# pmm.net
KiCad netlist of a schematic drawn in EAGLE
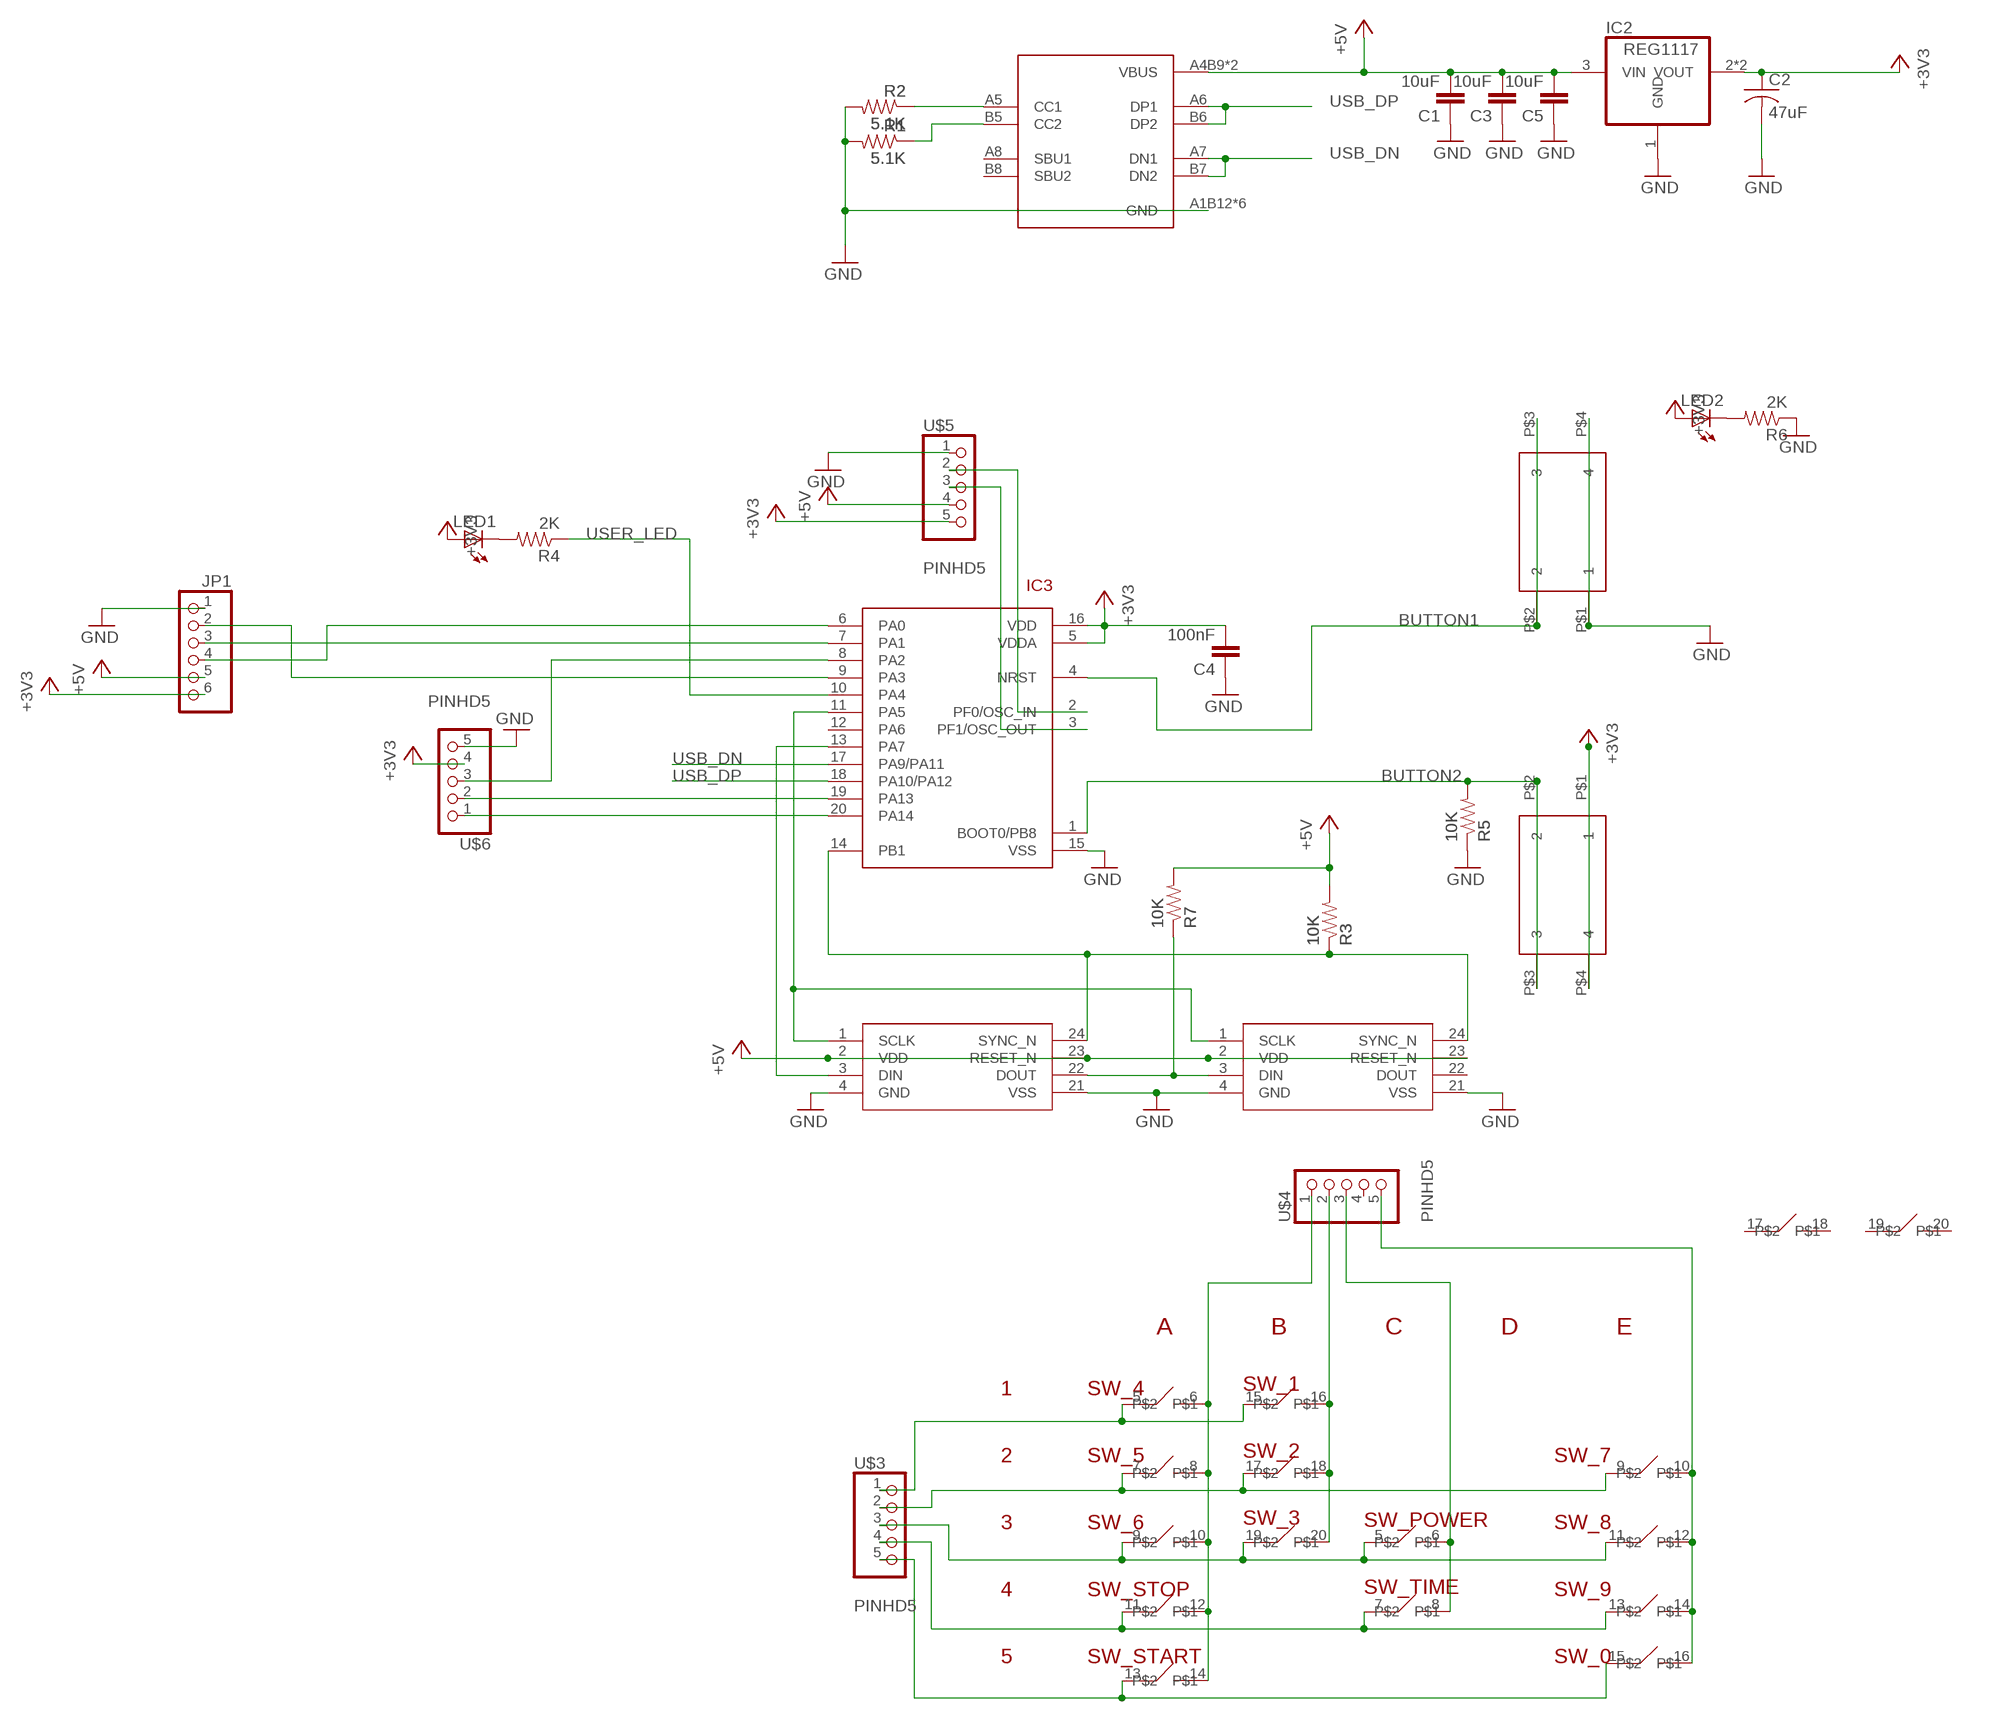
[diagram p0: schematic, sheet 1]

(export (version "E")
  (design (tool "Eeschema 10.0.6"))
  (components
    (comp (ref "C1")
      (value "10uF")
      (footprint "eagle-import:0805@1")
      (libsource (lib "eagle-import") (part "CAP0805"))
    )
    (comp (ref "C2")
      (value "47uF")
      (footprint "eagle-import:C1210")
      (libsource (lib "eagle-import") (part "C-USC1210"))
    )
    (comp (ref "C3")
      (value "10uF")
      (footprint "eagle-import:0805@1")
      (libsource (lib "eagle-import") (part "CAP0805"))
    )
    (comp (ref "C4")
      (value "100nF")
      (footprint "eagle-import:0805@1")
      (libsource (lib "eagle-import") (part "CAP0805"))
    )
    (comp (ref "C5")
      (value "10uF")
      (footprint "eagle-import:0805@1")
      (libsource (lib "eagle-import") (part "CAP0805"))
    )
    (comp (ref "IC2")
      (value "REG1117")
      (footprint "eagle-import:SOT223")
      (libsource (lib "eagle-import") (part "REG1117"))
    )
    (comp (ref "IC3")
      (value "STM32F042F4")
      (footprint "eagle-import:TSSOP20")
      (libsource (lib "eagle-import") (part "STM32F042F4"))
    )
    (comp (ref "JP1")
      (value "PINHD-1X6CB")
      (footprint "eagle-import:1X06-CLEANBIG")
      (libsource (lib "eagle-import") (part "PINHD-1X6CB"))
    )
    (comp (ref "LED1")
      (value "LEDCHIP-LED0805")
      (footprint "eagle-import:CHIP-LED0805")
      (libsource (lib "eagle-import") (part "LEDCHIP-LED0805"))
    )
    (comp (ref "LED2")
      (value "LEDCHIP-LED0805")
      (footprint "eagle-import:CHIP-LED0805")
      (libsource (lib "eagle-import") (part "LEDCHIP-LED0805"))
    )
    (comp (ref "R1")
      (value "5.1K")
      (footprint "eagle-import:0805")
      (libsource (lib "eagle-import") (part "joyAnalog_RESISTOR0805-RES"))
    )
    (comp (ref "R2")
      (value "5.1K")
      (footprint "eagle-import:0805")
      (libsource (lib "eagle-import") (part "joyAnalog_RESISTOR0805-RES"))
    )
    (comp (ref "R3")
      (value "10K")
      (footprint "eagle-import:0805")
      (libsource (lib "eagle-import") (part "joyAnalog_RESISTOR0805-RES"))
    )
    (comp (ref "R4")
      (value "2K")
      (footprint "eagle-import:0805")
      (libsource (lib "eagle-import") (part "RESISTOR0805-RES"))
    )
    (comp (ref "R5")
      (value "10K")
      (footprint "eagle-import:0805")
      (libsource (lib "eagle-import") (part "joyAnalog_RESISTOR0805-RES"))
    )
    (comp (ref "R6")
      (value "2K")
      (footprint "eagle-import:0805")
      (libsource (lib "eagle-import") (part "RESISTOR0805-RES"))
    )
    (comp (ref "R7")
      (value "10K")
      (footprint "eagle-import:0805")
      (libsource (lib "eagle-import") (part "joyAnalog_RESISTOR0805-RES"))
    )
    (comp (ref "SW3")
      (value "324_SW")
      (footprint "eagle-import:342_SWICH_FOOT")
      (libsource (lib "eagle-import") (part "324_SW"))
    )
    (comp (ref "SW4")
      (value "324_SW")
      (footprint "eagle-import:342_SWICH_FOOT")
      (libsource (lib "eagle-import") (part "324_SW"))
    )
    (comp (ref "U$1")
      (value "ADG714_SEPERATE")
      (footprint "eagle-import:TSSOP-24")
      (libsource (lib "eagle-import") (part "ADG714_SEPERATE"))
    )
    (comp (ref "U$2")
      (value "ADG714_SEPERATE")
      (footprint "eagle-import:TSSOP-24")
      (libsource (lib "eagle-import") (part "ADG714_SEPERATE"))
    )
    (comp (ref "U$3")
      (value "PINHD5")
      (footprint "eagle-import:1X05")
      (libsource (lib "eagle-import") (part "PINHD5"))
    )
    (comp (ref "U$4")
      (value "PINHD5")
      (footprint "eagle-import:1X05")
      (libsource (lib "eagle-import") (part "PINHD5"))
    )
    (comp (ref "U$5")
      (value "PINHD5")
      (footprint "eagle-import:1X05")
      (libsource (lib "eagle-import") (part "PINHD5"))
    )
    (comp (ref "U$6")
      (value "PINHD5")
      (footprint "eagle-import:1X05")
      (libsource (lib "eagle-import") (part "PINHD5"))
    )
    (comp (ref "U2")
      (value "USBC_16P")
      (footprint "eagle-import:USBC_16P_FOOT")
      (libsource (lib "eagle-import") (part "USBC_16P"))
    )
  )
  (nets
    (net (code "1") (name "+3V3") (class "Default")
      (node (ref "C2") (pin "1") (pinfunction "1_1") (pintype "passive"))
      (node (ref "C4") (pin "2") (pinfunction "2_2") (pintype "passive"))
      (node (ref "IC2") (pin "2") (pinfunction "VOUT_2") (pintype "output"))
      (node (ref "IC2") (pin "4") (pinfunction "VOUT_4") (pintype "output"))
      (node (ref "IC3") (pin "16") (pinfunction "VDD_16") (pintype "bidirectional"))
      (node (ref "IC3") (pin "5") (pinfunction "VDDA_5") (pintype "bidirectional"))
      (node (ref "JP1") (pin "6") (pinfunction "6_6") (pintype "passive"))
      (node (ref "LED1") (pin "A") (pinfunction "A_A") (pintype "passive"))
      (node (ref "LED2") (pin "A") (pinfunction "A_A") (pintype "passive"))
      (node (ref "SW4") (pin "P$1") (pinfunction "1_P$1") (pintype "bidirectional"))
      (node (ref "SW4") (pin "P$4") (pinfunction "4_P$4") (pintype "bidirectional"))
      (node (ref "U$5") (pin "5") (pinfunction "5_5") (pintype "passive"))
      (node (ref "U$6") (pin "4") (pinfunction "4_4") (pintype "passive"))
    )
    (net (code "2") (name "+5V") (class "Default")
      (node (ref "C1") (pin "2") (pinfunction "2_2") (pintype "passive"))
      (node (ref "C3") (pin "2") (pinfunction "2_2") (pintype "passive"))
      (node (ref "C5") (pin "2") (pinfunction "2_2") (pintype "passive"))
      (node (ref "IC2") (pin "3") (pinfunction "VIN_3") (pintype "input"))
      (node (ref "JP1") (pin "5") (pinfunction "5_5") (pintype "passive"))
      (node (ref "R3") (pin "2") (pinfunction "2_2") (pintype "passive"))
      (node (ref "R7") (pin "2") (pinfunction "2_2") (pintype "passive"))
      (node (ref "U$1") (pin "2") (pinfunction "VDD_2") (pintype "bidirectional"))
      (node (ref "U$1") (pin "23") (pinfunction "RESET_N_23") (pintype "bidirectional"))
      (node (ref "U$2") (pin "2") (pinfunction "VDD_2") (pintype "bidirectional"))
      (node (ref "U$2") (pin "23") (pinfunction "RESET_N_23") (pintype "bidirectional"))
      (node (ref "U$5") (pin "4") (pinfunction "4_4") (pintype "passive"))
      (node (ref "U2") (pin "A4B9") (pinfunction "VBUS_A4B9") (pintype "bidirectional"))
      (node (ref "U2") (pin "B4A9") (pinfunction "VBUS_B4A9") (pintype "bidirectional"))
    )
    (net (code "3") (name "/BUTTON1") (class "Default")
      (node (ref "IC3") (pin "4") (pinfunction "NRST_4") (pintype "bidirectional"))
      (node (ref "SW3") (pin "P$2") (pinfunction "2_P$2") (pintype "bidirectional"))
      (node (ref "SW3") (pin "P$3") (pinfunction "3_P$3") (pintype "bidirectional"))
    )
    (net (code "4") (name "/BUTTON2") (class "Default")
      (node (ref "IC3") (pin "1") (pinfunction "BOOT0/PB8_1") (pintype "bidirectional"))
      (node (ref "R5") (pin "2") (pinfunction "2_2") (pintype "passive"))
      (node (ref "SW4") (pin "P$2") (pinfunction "2_P$2") (pintype "bidirectional"))
      (node (ref "SW4") (pin "P$3") (pinfunction "3_P$3") (pintype "bidirectional"))
    )
    (net (code "5") (name "/USB_DN") (class "Default")
      (node (ref "IC3") (pin "17") (pinfunction "PA9/PA11_17") (pintype "bidirectional"))
      (node (ref "U2") (pin "A7") (pinfunction "DN1_A7") (pintype "bidirectional"))
      (node (ref "U2") (pin "B7") (pinfunction "DN2_B7") (pintype "bidirectional"))
    )
    (net (code "6") (name "/USB_DP") (class "Default")
      (node (ref "IC3") (pin "18") (pinfunction "PA10/PA12_18") (pintype "bidirectional"))
      (node (ref "U2") (pin "A6") (pinfunction "DP1_A6") (pintype "bidirectional"))
      (node (ref "U2") (pin "B6") (pinfunction "DP2_B6") (pintype "bidirectional"))
    )
    (net (code "7") (name "/USER_LED") (class "Default")
      (node (ref "IC3") (pin "10") (pinfunction "PA4_10") (pintype "bidirectional"))
      (node (ref "R4") (pin "1") (pinfunction "1_1") (pintype "passive"))
    )
    (net (code "8") (name "GND") (class "Default")
      (node (ref "C1") (pin "1") (pinfunction "1_1") (pintype "passive"))
      (node (ref "C2") (pin "2") (pinfunction "2_2") (pintype "passive"))
      (node (ref "C3") (pin "1") (pinfunction "1_1") (pintype "passive"))
      (node (ref "C4") (pin "1") (pinfunction "1_1") (pintype "passive"))
      (node (ref "C5") (pin "1") (pinfunction "1_1") (pintype "passive"))
      (node (ref "IC2") (pin "1") (pinfunction "GND_1") (pintype "power_in"))
      (node (ref "IC3") (pin "15") (pinfunction "VSS_15") (pintype "bidirectional"))
      (node (ref "JP1") (pin "1") (pinfunction "1_1") (pintype "passive"))
      (node (ref "R1") (pin "2") (pinfunction "2_2") (pintype "passive"))
      (node (ref "R2") (pin "2") (pinfunction "2_2") (pintype "passive"))
      (node (ref "R5") (pin "1") (pinfunction "1_1") (pintype "passive"))
      (node (ref "R6") (pin "1") (pinfunction "1_1") (pintype "passive"))
      (node (ref "SW3") (pin "P$1") (pinfunction "1_P$1") (pintype "bidirectional"))
      (node (ref "SW3") (pin "P$4") (pinfunction "4_P$4") (pintype "bidirectional"))
      (node (ref "U$1") (pin "21") (pinfunction "VSS_21") (pintype "bidirectional"))
      (node (ref "U$1") (pin "4") (pinfunction "GND_4") (pintype "bidirectional"))
      (node (ref "U$2") (pin "21") (pinfunction "VSS_21") (pintype "bidirectional"))
      (node (ref "U$2") (pin "4") (pinfunction "GND_4") (pintype "bidirectional"))
      (node (ref "U$5") (pin "1") (pinfunction "1_1") (pintype "passive"))
      (node (ref "U$6") (pin "5") (pinfunction "5_5") (pintype "passive"))
      (node (ref "U2") (pin "A1B12") (pinfunction "GND_A1B12") (pintype "bidirectional"))
      (node (ref "U2") (pin "B11A12") (pinfunction "GND_B11A12") (pintype "bidirectional"))
      (node (ref "U2") (pin "P$13") (pinfunction "GND_P$13") (pintype "bidirectional"))
      (node (ref "U2") (pin "P$14") (pinfunction "GND_P$14") (pintype "bidirectional"))
      (node (ref "U2") (pin "P$15") (pinfunction "GND_P$15") (pintype "bidirectional"))
      (node (ref "U2") (pin "P$16") (pinfunction "GND_P$16") (pintype "bidirectional"))
    )
    (net (code "9") (name "Net-(IC3-PA0)") (class "Default")
      (node (ref "IC3") (pin "6") (pinfunction "PA0_6") (pintype "bidirectional"))
      (node (ref "JP1") (pin "4") (pinfunction "4_4") (pintype "passive"))
    )
    (net (code "10") (name "Net-(IC3-PA1)") (class "Default")
      (node (ref "IC3") (pin "7") (pinfunction "PA1_7") (pintype "bidirectional"))
      (node (ref "JP1") (pin "3") (pinfunction "3_3") (pintype "passive"))
    )
    (net (code "11") (name "Net-(IC3-PA2)") (class "Default")
      (node (ref "IC3") (pin "8") (pinfunction "PA2_8") (pintype "bidirectional"))
      (node (ref "U$6") (pin "3") (pinfunction "3_3") (pintype "passive"))
    )
    (net (code "12") (name "Net-(IC3-PA3)") (class "Default")
      (node (ref "IC3") (pin "9") (pinfunction "PA3_9") (pintype "bidirectional"))
      (node (ref "JP1") (pin "2") (pinfunction "2_2") (pintype "passive"))
    )
    (net (code "13") (name "Net-(IC3-PA5)") (class "Default")
      (node (ref "IC3") (pin "11") (pinfunction "PA5_11") (pintype "bidirectional"))
      (node (ref "U$1") (pin "1") (pinfunction "SCLK_1") (pintype "bidirectional"))
      (node (ref "U$2") (pin "1") (pinfunction "SCLK_1") (pintype "bidirectional"))
    )
    (net (code "14") (name "Net-(IC3-PA7)") (class "Default")
      (node (ref "IC3") (pin "13") (pinfunction "PA7_13") (pintype "bidirectional"))
      (node (ref "U$1") (pin "3") (pinfunction "DIN_3") (pintype "bidirectional"))
    )
    (net (code "15") (name "Net-(IC3-PA13)") (class "Default")
      (node (ref "IC3") (pin "19") (pinfunction "PA13_19") (pintype "bidirectional"))
      (node (ref "U$6") (pin "2") (pinfunction "2_2") (pintype "passive"))
    )
    (net (code "16") (name "Net-(IC3-PA14)") (class "Default")
      (node (ref "IC3") (pin "20") (pinfunction "PA14_20") (pintype "bidirectional"))
      (node (ref "U$6") (pin "1") (pinfunction "1_1") (pintype "passive"))
    )
    (net (code "17") (name "Net-(IC3-PB1)") (class "Default")
      (node (ref "IC3") (pin "14") (pinfunction "PB1_14") (pintype "bidirectional"))
      (node (ref "R3") (pin "1") (pinfunction "1_1") (pintype "passive"))
      (node (ref "U$1") (pin "24") (pinfunction "SYNC_N_24") (pintype "bidirectional"))
      (node (ref "U$2") (pin "24") (pinfunction "SYNC_N_24") (pintype "bidirectional"))
    )
    (net (code "18") (name "Net-(IC3-PF0{slash}OSC_IN)") (class "Default")
      (node (ref "IC3") (pin "2") (pinfunction "PF0/OSC_IN_2") (pintype "bidirectional"))
      (node (ref "U$5") (pin "2") (pinfunction "2_2") (pintype "passive"))
    )
    (net (code "19") (name "Net-(IC3-PF1{slash}OSC_OUT)") (class "Default")
      (node (ref "IC3") (pin "3") (pinfunction "PF1/OSC_OUT_3") (pintype "bidirectional"))
      (node (ref "U$5") (pin "3") (pinfunction "3_3") (pintype "passive"))
    )
    (net (code "20") (name "Net-(LED1-PadC)") (class "Default")
      (node (ref "LED1") (pin "C") (pinfunction "C_C") (pintype "passive"))
      (node (ref "R4") (pin "2") (pinfunction "2_2") (pintype "passive"))
    )
    (net (code "21") (name "Net-(LED2-PadC)") (class "Default")
      (node (ref "LED2") (pin "C") (pinfunction "C_C") (pintype "passive"))
      (node (ref "R6") (pin "2") (pinfunction "2_2") (pintype "passive"))
    )
    (net (code "22") (name "Net-(U$1A-DOUT)") (class "Default")
      (node (ref "R7") (pin "1") (pinfunction "1_1") (pintype "passive"))
      (node (ref "U$1") (pin "22") (pinfunction "DOUT_22") (pintype "bidirectional"))
      (node (ref "U$2") (pin "3") (pinfunction "DIN_3") (pintype "bidirectional"))
    )
    (net (code "23") (name "Net-(U$1B-P$1)") (class "Default")
      (node (ref "U$1") (pin "15") (pinfunction "P$1_15") (pintype "bidirectional"))
      (node (ref "U$1") (pin "5") (pinfunction "P$1_5") (pintype "bidirectional"))
      (node (ref "U$3") (pin "1") (pinfunction "1_1") (pintype "passive"))
    )
    (net (code "24") (name "Net-(U$1B-P$2)") (class "Default")
      (node (ref "U$1") (pin "10") (pinfunction "P$2_10") (pintype "bidirectional"))
      (node (ref "U$1") (pin "12") (pinfunction "P$2_12") (pintype "bidirectional"))
      (node (ref "U$1") (pin "14") (pinfunction "P$2_14") (pintype "bidirectional"))
      (node (ref "U$1") (pin "6") (pinfunction "P$2_6") (pintype "bidirectional"))
      (node (ref "U$1") (pin "8") (pinfunction "P$2_8") (pintype "bidirectional"))
      (node (ref "U$4") (pin "1") (pinfunction "1_1") (pintype "passive"))
    )
    (net (code "25") (name "Net-(U$1C-P$1)") (class "Default")
      (node (ref "U$1") (pin "17") (pinfunction "P$1_17") (pintype "bidirectional"))
      (node (ref "U$1") (pin "7") (pinfunction "P$1_7") (pintype "bidirectional"))
      (node (ref "U$2") (pin "9") (pinfunction "P$1_9") (pintype "bidirectional"))
      (node (ref "U$3") (pin "2") (pinfunction "2_2") (pintype "passive"))
    )
    (net (code "26") (name "Net-(U$1D-P$1)") (class "Default")
      (node (ref "U$1") (pin "19") (pinfunction "P$1_19") (pintype "bidirectional"))
      (node (ref "U$1") (pin "9") (pinfunction "P$1_9") (pintype "bidirectional"))
      (node (ref "U$2") (pin "11") (pinfunction "P$1_11") (pintype "bidirectional"))
      (node (ref "U$2") (pin "5") (pinfunction "P$1_5") (pintype "bidirectional"))
      (node (ref "U$3") (pin "3") (pinfunction "3_3") (pintype "passive"))
    )
    (net (code "27") (name "Net-(U$1E-P$1)") (class "Default")
      (node (ref "U$1") (pin "11") (pinfunction "P$1_11") (pintype "bidirectional"))
      (node (ref "U$2") (pin "13") (pinfunction "P$1_13") (pintype "bidirectional"))
      (node (ref "U$2") (pin "7") (pinfunction "P$1_7") (pintype "bidirectional"))
      (node (ref "U$3") (pin "4") (pinfunction "4_4") (pintype "passive"))
    )
    (net (code "28") (name "Net-(U$1F-P$1)") (class "Default")
      (node (ref "U$1") (pin "13") (pinfunction "P$1_13") (pintype "bidirectional"))
      (node (ref "U$2") (pin "15") (pinfunction "P$1_15") (pintype "bidirectional"))
      (node (ref "U$3") (pin "5") (pinfunction "5_5") (pintype "passive"))
    )
    (net (code "29") (name "Net-(U$1G-P$2)") (class "Default")
      (node (ref "U$1") (pin "16") (pinfunction "P$2_16") (pintype "bidirectional"))
      (node (ref "U$1") (pin "18") (pinfunction "P$2_18") (pintype "bidirectional"))
      (node (ref "U$1") (pin "20") (pinfunction "P$2_20") (pintype "bidirectional"))
      (node (ref "U$4") (pin "2") (pinfunction "2_2") (pintype "passive"))
    )
    (net (code "30") (name "Net-(U$2B-P$2)") (class "Default")
      (node (ref "U$2") (pin "6") (pinfunction "P$2_6") (pintype "bidirectional"))
      (node (ref "U$2") (pin "8") (pinfunction "P$2_8") (pintype "bidirectional"))
      (node (ref "U$4") (pin "3") (pinfunction "3_3") (pintype "passive"))
    )
    (net (code "31") (name "Net-(U$2D-P$2)") (class "Default")
      (node (ref "U$2") (pin "10") (pinfunction "P$2_10") (pintype "bidirectional"))
      (node (ref "U$2") (pin "12") (pinfunction "P$2_12") (pintype "bidirectional"))
      (node (ref "U$2") (pin "14") (pinfunction "P$2_14") (pintype "bidirectional"))
      (node (ref "U$2") (pin "16") (pinfunction "P$2_16") (pintype "bidirectional"))
      (node (ref "U$4") (pin "5") (pinfunction "5_5") (pintype "passive"))
    )
    (net (code "32") (name "Net-(U2-CC1)") (class "Default")
      (node (ref "R2") (pin "1") (pinfunction "1_1") (pintype "passive"))
      (node (ref "U2") (pin "A5") (pinfunction "CC1_A5") (pintype "bidirectional"))
    )
    (net (code "33") (name "Net-(U2-CC2)") (class "Default")
      (node (ref "R1") (pin "1") (pinfunction "1_1") (pintype "passive"))
      (node (ref "U2") (pin "B5") (pinfunction "CC2_B5") (pintype "bidirectional"))
    )
    (net (code "34") (name "unconnected-(IC3-PA6-Pad12)") (class "Default")
      (node (ref "IC3") (pin "12") (pinfunction "PA6_12") (pintype "bidirectional"))
    )
    (net (code "35") (name "unconnected-(U$2A-DOUT-Pad22)") (class "Default")
      (node (ref "U$2") (pin "22") (pinfunction "DOUT_22") (pintype "bidirectional"))
    )
    (net (code "36") (name "unconnected-(U$2H-P$1-Pad17)") (class "Default")
      (node (ref "U$2") (pin "17") (pinfunction "P$1_17") (pintype "bidirectional"))
    )
    (net (code "37") (name "unconnected-(U$2H-P$2-Pad18)") (class "Default")
      (node (ref "U$2") (pin "18") (pinfunction "P$2_18") (pintype "bidirectional"))
    )
    (net (code "38") (name "unconnected-(U$2I-P$1-Pad19)") (class "Default")
      (node (ref "U$2") (pin "19") (pinfunction "P$1_19") (pintype "bidirectional"))
    )
    (net (code "39") (name "unconnected-(U$2I-P$2-Pad20)") (class "Default")
      (node (ref "U$2") (pin "20") (pinfunction "P$2_20") (pintype "bidirectional"))
    )
    (net (code "40") (name "unconnected-(U$4-Pad4)") (class "Default")
      (node (ref "U$4") (pin "4") (pinfunction "4_4") (pintype "passive"))
    )
    (net (code "41") (name "unconnected-(U2-SBU1-PadA8)") (class "Default")
      (node (ref "U2") (pin "A8") (pinfunction "SBU1_A8") (pintype "bidirectional"))
    )
    (net (code "42") (name "unconnected-(U2-SBU2-PadB8)") (class "Default")
      (node (ref "U2") (pin "B8") (pinfunction "SBU2_B8") (pintype "bidirectional"))
    )
  )
)
